# Buzzer.net
KiCad netlist of a schematic drawn in Altium Designer
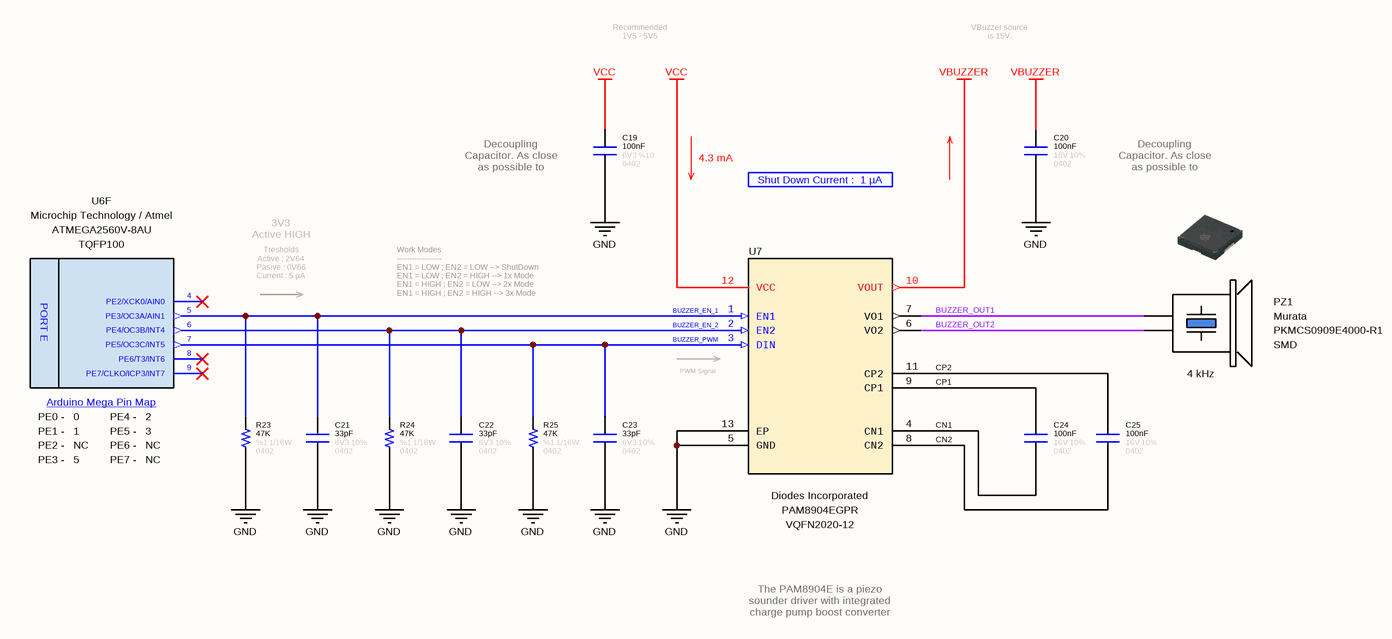
[diagram p0: Buzzer.SchDoc]

(export (version "E")
  (design (tool "Eeschema 10.0.6"))
  (components
    (comp (ref "C19")
      (value "100nF")
      (footprint "CAPACITOR_0402")
      (description "Capacitor - 100nF [0402-6V3] (Ceramic)")
      (fields
        (field (name "MANUFACTURER PART NUMBER") "04026D104KAT4A")
        (field (name "TOLERANCE") "%10")
        (field (name "VOLTAGE") "6V3")
        (field (name "CASE") "0402")
        (field (name "Comment") "Capacitor - 100nF [0402] (Ceramic)")
      )
      (libsource (lib "P101DA_Library") (part "Capacitor - 100nF [0402-6V3]"))
    )
    (comp (ref "C20")
      (value "100nF")
      (footprint "CAPACITOR_0402")
      (description "Multilayer Ceramic Capacitors - SMD - 16V 100nF X7R 0402 10%")
      (fields
        (field (name "MANUFACTURER PART NUMBER") "0402YC104KAT2A")
        (field (name "TOLERANCE") "10%")
        (field (name "CASE") "0402")
        (field (name "VOLTAGE") "16V")
        (field (name "Comment") "Capacitor - 100nF [0402] (Ceramic)")
      )
      (libsource (lib "P101DA_Library") (part "Capacitor - 100nF [0402-16V]"))
    )
    (comp (ref "C21")
      (value "33pF")
      (footprint "CAPACITOR_0402")
      (description "Capacitor - 33pF [0402] (Ceramic)")
      (fields
        (field (name "MANUFACTURER PART NUMBER") "C0402C330J9RACAUTO")
        (field (name "TOLERANCE") "10%")
        (field (name "CASE") "0402")
        (field (name "VOLTAGE") "6V3")
      )
      (libsource (lib "P101DA_Library") (part "Capacitor - 33pF [0402-6V3]"))
    )
    (comp (ref "C22")
      (value "33pF")
      (footprint "CAPACITOR_0402")
      (description "Capacitor - 33pF [0402] (Ceramic)")
      (fields
        (field (name "MANUFACTURER PART NUMBER") "C0402C330J9RACAUTO")
        (field (name "TOLERANCE") "10%")
        (field (name "CASE") "0402")
        (field (name "VOLTAGE") "6V3")
      )
      (libsource (lib "P101DA_Library") (part "Capacitor - 33pF [0402-6V3]"))
    )
    (comp (ref "C23")
      (value "33pF")
      (footprint "CAPACITOR_0402")
      (description "Capacitor - 33pF [0402] (Ceramic)")
      (fields
        (field (name "MANUFACTURER PART NUMBER") "C0402C330J9RACAUTO")
        (field (name "TOLERANCE") "10%")
        (field (name "CASE") "0402")
        (field (name "VOLTAGE") "6V3")
      )
      (libsource (lib "P101DA_Library") (part "Capacitor - 33pF [0402-6V3]"))
    )
    (comp (ref "C24")
      (value "100nF")
      (footprint "CAPACITOR_0402")
      (description "Multilayer Ceramic Capacitors - SMD - 16V 100nF X7R 0402 10%")
      (fields
        (field (name "MANUFACTURER PART NUMBER") "0402YC104KAT2A")
        (field (name "TOLERANCE") "10%")
        (field (name "CASE") "0402")
        (field (name "VOLTAGE") "16V")
        (field (name "Comment") "Capacitor - 100nF [0402] (Ceramic)")
      )
      (libsource (lib "P101DA_Library") (part "Capacitor - 100nF [0402-16V]"))
    )
    (comp (ref "C25")
      (value "100nF")
      (footprint "CAPACITOR_0402")
      (description "Multilayer Ceramic Capacitors - SMD - 16V 100nF X7R 0402 10%")
      (fields
        (field (name "MANUFACTURER PART NUMBER") "0402YC104KAT2A")
        (field (name "TOLERANCE") "10%")
        (field (name "CASE") "0402")
        (field (name "VOLTAGE") "16V")
        (field (name "Comment") "Capacitor - 100nF [0402] (Ceramic)")
      )
      (libsource (lib "P101DA_Library") (part "Capacitor - 100nF [0402-16V]"))
    )
    (comp (ref "PZ1")
      (value "PKMCS0909E4000-R1")
      (footprint "Murata - Buzzer")
      (description "MURATA - PKMCS0909E4000-R1 - Transducer, Piezo, Sounder, Sounder, -12.5 VDC, 12.5 VDC, 65 dB")
      (fields
        (field (name "MANUFACTURER NAME") "Murata")
        (field (name "MANUFACTURER PART NUMBER") "PKMCS0909E4000-R1")
        (field (name "CASE") "SMD")
        (field (name "FREQUENCY") "4 kHz")
      )
      (libsource (lib "P101DA_Library") (part "Buzzer - PKMCS0909E4000-R1"))
    )
    (comp (ref "R23")
      (value "47K")
      (footprint "RESISTOR_0402")
      (description "Thick Film Resistors - SMD 1/16 W 47 KOhm 1%")
      (fields
        (field (name "MANUFACTURER PART NUMBER") "CRCW040247K0FKED")
        (field (name "TOLERANCE") "%1")
        (field (name "CASE") "0402")
        (field (name "POWER") "1/16W")
        (field (name "Comment") "47K - 0402 - %1 - 1/16W")
      )
      (libsource (lib "P101DA_Library") (part "Resistor - 47K [0402]"))
    )
    (comp (ref "R24")
      (value "47K")
      (footprint "RESISTOR_0402")
      (description "Thick Film Resistors - SMD 1/16 W 47 KOhm 1%")
      (fields
        (field (name "MANUFACTURER PART NUMBER") "CRCW040247K0FKED")
        (field (name "TOLERANCE") "%1")
        (field (name "CASE") "0402")
        (field (name "POWER") "1/16W")
        (field (name "Comment") "47K - 0402 - %1 - 1/16W")
      )
      (libsource (lib "P101DA_Library") (part "Resistor - 47K [0402]"))
    )
    (comp (ref "R25")
      (value "47K")
      (footprint "RESISTOR_0402")
      (description "Thick Film Resistors - SMD 1/16 W 47 KOhm 1%")
      (fields
        (field (name "MANUFACTURER PART NUMBER") "CRCW040247K0FKED")
        (field (name "TOLERANCE") "%1")
        (field (name "CASE") "0402")
        (field (name "POWER") "1/16W")
        (field (name "Comment") "47K - 0402 - %1 - 1/16W")
      )
      (libsource (lib "P101DA_Library") (part "Resistor - 47K [0402]"))
    )
    (comp (ref "U6")
      (value "ATMEGA2560V-8AU")
      (footprint "TQFP-100")
      (description "ATmega Series 256 KB Flash 8 KB SRAM 8 MHz 8-Bit Microcontroller - TQFP-100")
      (fields
        (field (name "MANUFACTURER NAME") "Microchip Technology / Atmel")
        (field (name "MANUFACTURER PART NUMBER") "ATMEGA2560V-8AU")
        (field (name "CASE") "TQFP100")
      )
      (libsource (lib "P101DA_Library") (part "IC - AtMega2560V-8AU"))
    )
    (comp (ref "U7")
      (value "PAM8904EGPR")
      (footprint "U-QFN2020-12")
      (description "27VPP Piezo Sounder Driver, 1.5 to 5.5V, 0.22mA")
      (fields
        (field (name "MANUFACTURER NAME") "Diodes Incorporated")
        (field (name "MANUFACTURER PART NUMBER") "PAM8904EGPR")
        (field (name "CASE") "VQFN2020-12")
      )
      (libsource (lib "P101DA_Library") (part "IC - PAM8904"))
    )
  )
  (nets
    (net (code "1") (name "/BUZZER_EN_1") (class "Default")
      (node (ref "C21") (pin "2") (pinfunction "2_2") (pintype "passive"))
      (node (ref "R23") (pin "2") (pinfunction "2_2") (pintype "passive"))
      (node (ref "U6") (pin "5") (pinfunction "PE3/OC3A/AIN1_5") (pintype "output"))
      (node (ref "U7") (pin "1") (pinfunction "EN1_1") (pintype "input"))
    )
    (net (code "2") (name "/BUZZER_EN_2") (class "Default")
      (node (ref "C22") (pin "2") (pinfunction "2_2") (pintype "passive"))
      (node (ref "R24") (pin "2") (pinfunction "2_2") (pintype "passive"))
      (node (ref "U6") (pin "6") (pinfunction "PE4/OC3B/INT4_6") (pintype "output"))
      (node (ref "U7") (pin "2") (pinfunction "EN2_2") (pintype "input"))
    )
    (net (code "3") (name "/BUZZER_OUT1") (class "Default")
      (node (ref "PZ1") (pin "1") (pinfunction "+_1") (pintype "passive"))
      (node (ref "U7") (pin "7") (pinfunction "VO1_7") (pintype "output"))
    )
    (net (code "4") (name "/BUZZER_OUT2") (class "Default")
      (node (ref "PZ1") (pin "2") (pinfunction "-_2") (pintype "passive"))
      (node (ref "U7") (pin "6") (pinfunction "VO2_6") (pintype "output"))
    )
    (net (code "5") (name "/BUZZER_PWM") (class "Default")
      (node (ref "C23") (pin "2") (pinfunction "2_2") (pintype "passive"))
      (node (ref "R25") (pin "2") (pinfunction "2_2") (pintype "passive"))
      (node (ref "U6") (pin "7") (pinfunction "PE5/OC3C/INT5_7") (pintype "output"))
      (node (ref "U7") (pin "3") (pinfunction "DIN_3") (pintype "input"))
    )
    (net (code "6") (name "/CN1") (class "Default")
      (node (ref "C24") (pin "1") (pinfunction "1_1") (pintype "passive"))
      (node (ref "U7") (pin "4") (pinfunction "CN1_4") (pintype "passive"))
    )
    (net (code "7") (name "/CN2") (class "Default")
      (node (ref "C25") (pin "1") (pinfunction "1_1") (pintype "passive"))
      (node (ref "U7") (pin "8") (pinfunction "CN2_8") (pintype "passive"))
    )
    (net (code "8") (name "/CP1") (class "Default")
      (node (ref "C24") (pin "2") (pinfunction "2_2") (pintype "passive"))
      (node (ref "U7") (pin "9") (pinfunction "CP1_9") (pintype "passive"))
    )
    (net (code "9") (name "/CP2") (class "Default")
      (node (ref "C25") (pin "2") (pinfunction "2_2") (pintype "passive"))
      (node (ref "U7") (pin "11") (pinfunction "CP2_11") (pintype "passive"))
    )
    (net (code "10") (name "GND") (class "Default")
      (node (ref "C19") (pin "1") (pinfunction "1_1") (pintype "passive"))
      (node (ref "C20") (pin "1") (pinfunction "1_1") (pintype "passive"))
      (node (ref "C21") (pin "1") (pinfunction "1_1") (pintype "passive"))
      (node (ref "C22") (pin "1") (pinfunction "1_1") (pintype "passive"))
      (node (ref "C23") (pin "1") (pinfunction "1_1") (pintype "passive"))
      (node (ref "R23") (pin "1") (pinfunction "1_1") (pintype "passive"))
      (node (ref "R24") (pin "1") (pinfunction "1_1") (pintype "passive"))
      (node (ref "R25") (pin "1") (pinfunction "1_1") (pintype "passive"))
      (node (ref "U7") (pin "13") (pinfunction "EP_13") (pintype "passive"))
      (node (ref "U7") (pin "5") (pinfunction "GND_5") (pintype "passive"))
    )
    (net (code "11") (name "VBUZZER") (class "Default")
      (node (ref "C20") (pin "2") (pinfunction "2_2") (pintype "passive"))
      (node (ref "U7") (pin "10") (pinfunction "VOUT_10") (pintype "output"))
    )
    (net (code "12") (name "VCC") (class "Default")
      (node (ref "C19") (pin "2") (pinfunction "2_2") (pintype "passive"))
      (node (ref "U7") (pin "12") (pinfunction "VCC_12") (pintype "power_in"))
    )
    (net (code "13") (name "unconnected-(U6F-PE2{slash}XCK0{slash}AIN0-Pad4)") (class "Default")
      (node (ref "U6") (pin "4") (pinfunction "PE2/XCK0/AIN0_4") (pintype "passive+no_connect"))
    )
    (net (code "14") (name "unconnected-(U6F-PE6{slash}T3{slash}INT6-Pad8)") (class "Default")
      (node (ref "U6") (pin "8") (pinfunction "PE6/T3/INT6_8") (pintype "passive+no_connect"))
    )
    (net (code "15") (name "unconnected-(U6F-PE7{slash}CLKO{slash}ICP3{slash}INT7-Pad9)") (class "Default")
      (node (ref "U6") (pin "9") (pinfunction "PE7/CLKO/ICP3/INT7_9") (pintype "passive+no_connect"))
    )
  )
)
